# Orbit_I_AnalougeEngine_V1_0.net
KiCad netlist of a schematic drawn in EAGLE
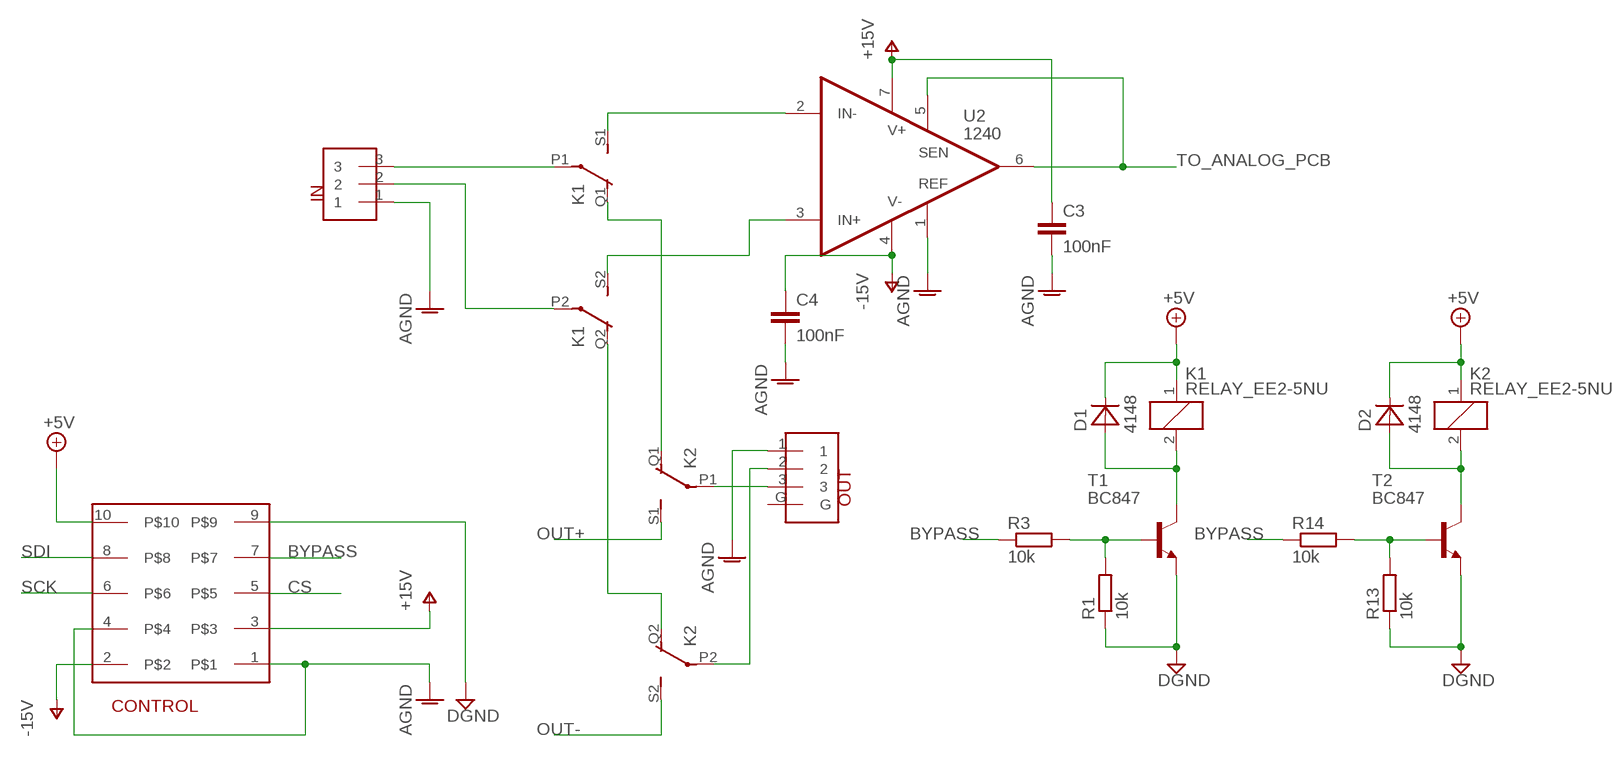
[diagram p0: schematic, sheet 1]
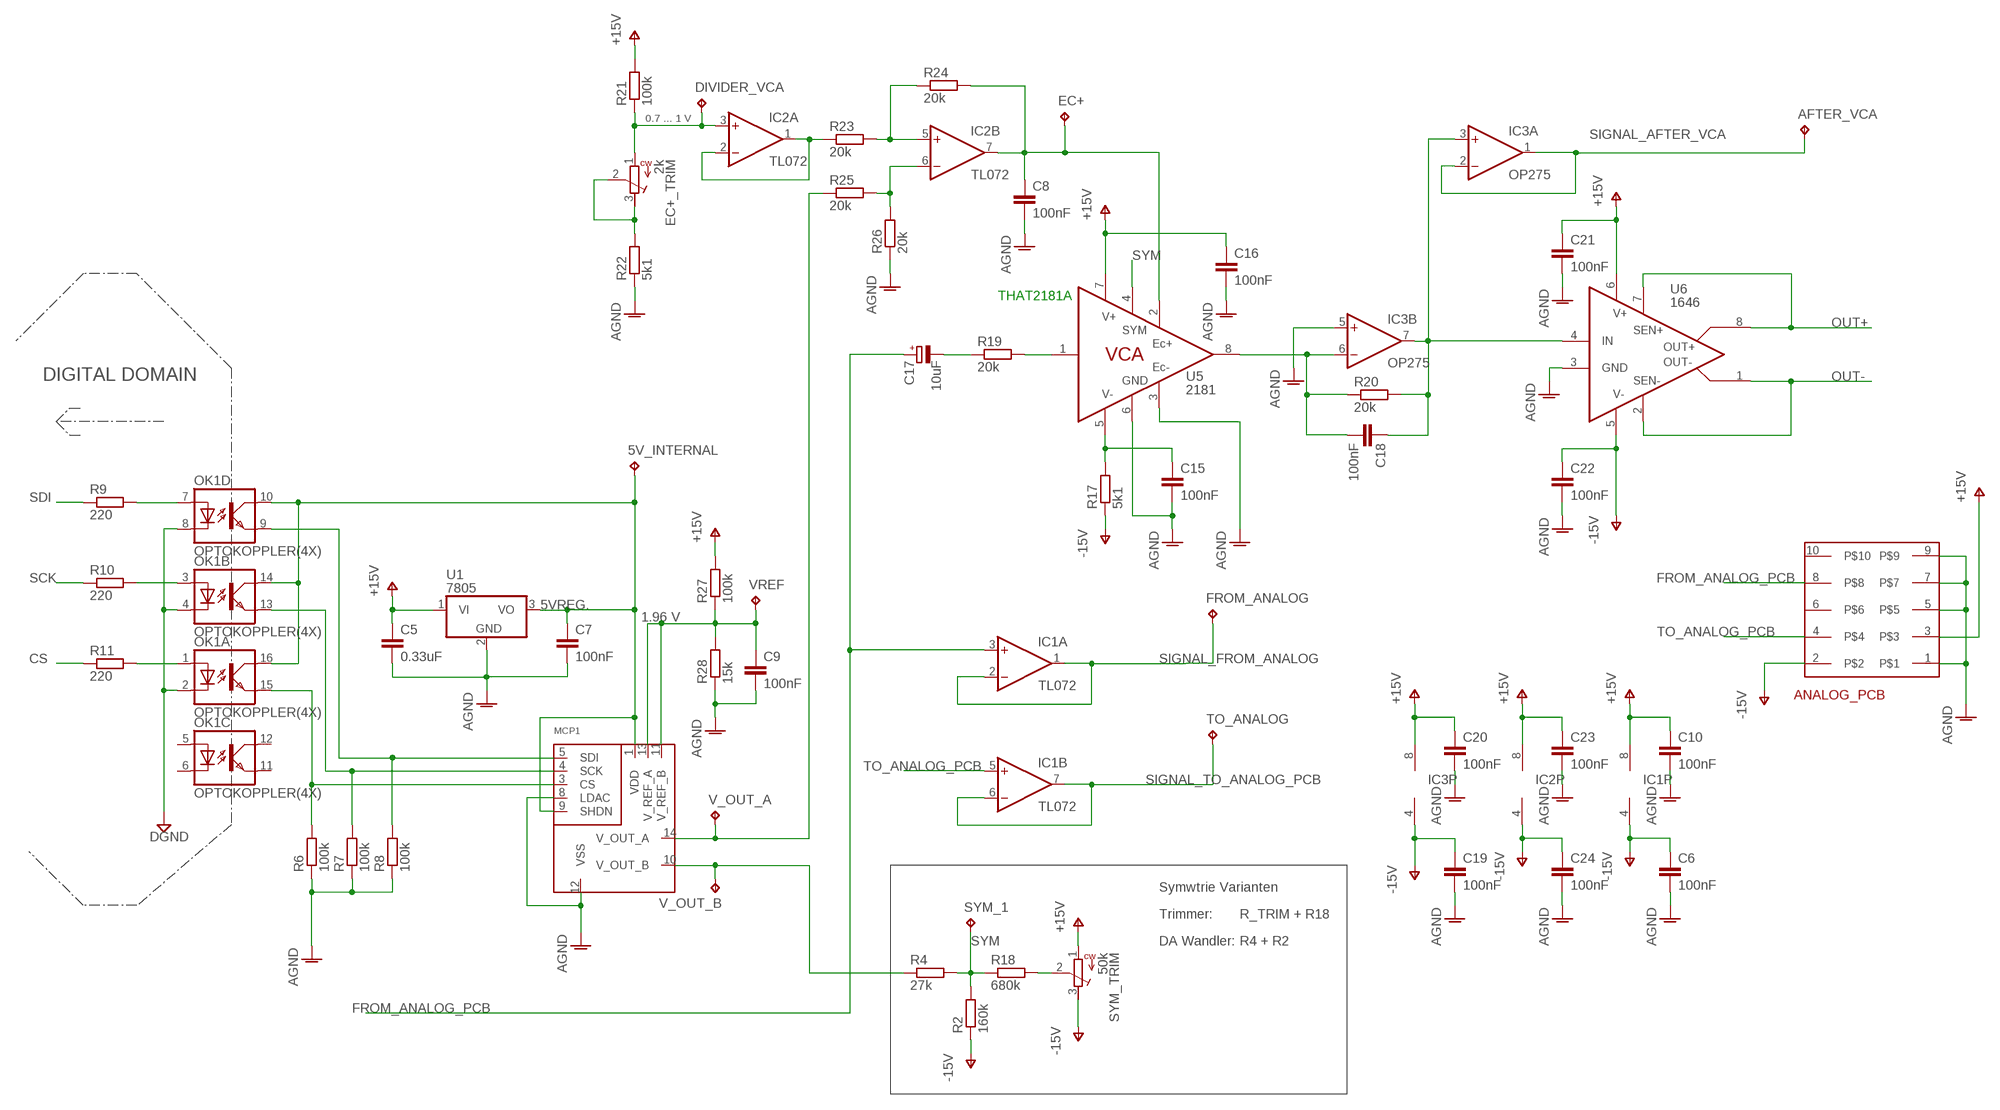
[diagram p1: schematic, sheet 2]

(export (version "E")
  (design (tool "Eeschema 10.0.6"))
  (components
    (comp (ref "C3")
      (value "100nF")
      (footprint "eagle-import:C0603")
      (libsource (lib "eagle-import") (part "KONDENSATOR_0603"))
    )
    (comp (ref "C4")
      (value "100nF")
      (footprint "eagle-import:C0603")
      (libsource (lib "eagle-import") (part "KONDENSATOR_0603"))
    )
    (comp (ref "CONTROL")
      (value "10PIN_HEADER_SMD")
      (footprint "eagle-import:87832-10")
      (libsource (lib "eagle-import") (part "10PIN_HEADER_SMD"))
    )
    (comp (ref "D1")
      (value "4148")
      (footprint "eagle-import:SOD323-R")
      (libsource (lib "eagle-import") (part "4148_SOD323"))
    )
    (comp (ref "D2")
      (value "4148")
      (footprint "eagle-import:SOD323-R")
      (libsource (lib "eagle-import") (part "4148_SOD323"))
    )
    (comp (ref "IN")
      (value "NEUTRIK_NC3FAH")
      (footprint "eagle-import:NEUTRIK_NC3FAH")
      (libsource (lib "eagle-import") (part "NEUTRIK_NC3FAH"))
    )
    (comp (ref "K1")
      (value "RELAY_EE2-5NU")
      (footprint "eagle-import:351")
      (libsource (lib "eagle-import") (part "RELAY_EE2-5NU"))
    )
    (comp (ref "K2")
      (value "RELAY_EE2-5NU")
      (footprint "eagle-import:351")
      (libsource (lib "eagle-import") (part "RELAY_EE2-5NU"))
    )
    (comp (ref "OUT")
      (value "NEUTRIK_NC3MAH")
      (footprint "eagle-import:NEUTRIK_NC3MAH")
      (libsource (lib "eagle-import") (part "NEUTRIK_NC3MAH"))
    )
    (comp (ref "R1")
      (value "10k")
      (footprint "eagle-import:R0805")
      (libsource (lib "eagle-import") (part "WIDERSTAND_0805R0805"))
    )
    (comp (ref "R3")
      (value "10k")
      (footprint "eagle-import:R0805")
      (libsource (lib "eagle-import") (part "WIDERSTAND_0805R0805"))
    )
    (comp (ref "R13")
      (value "10k")
      (footprint "eagle-import:R0805")
      (libsource (lib "eagle-import") (part "WIDERSTAND_0805R0805"))
    )
    (comp (ref "R14")
      (value "10k")
      (footprint "eagle-import:R0805")
      (libsource (lib "eagle-import") (part "WIDERSTAND_0805R0805"))
    )
    (comp (ref "T1")
      (value "BC847")
      (footprint "eagle-import:SOT23")
      (libsource (lib "eagle-import") (part "BC847"))
    )
    (comp (ref "T2")
      (value "BC847")
      (footprint "eagle-import:SOT23")
      (libsource (lib "eagle-import") (part "BC847"))
    )
    (comp (ref "U2")
      (value "1240")
      (footprint "eagle-import:SO08")
      (libsource (lib "eagle-import") (part "THAT1240SO8-U"))
    )
    (comp (ref "5V_INTERNAL")
      (value "TPTHT")
      (footprint "eagle-import:THT_PIN")
      (libsource (lib "eagle-import") (part "TPTHT"))
    )
    (comp (ref "AFTER_VCA")
      (value "TPTHT")
      (footprint "eagle-import:THT_PIN")
      (libsource (lib "eagle-import") (part "TPTHT"))
    )
    (comp (ref "ANALOG_PCB")
      (value "10PIN_HEADER_SMD")
      (footprint "eagle-import:87832-10")
      (libsource (lib "eagle-import") (part "10PIN_HEADER_SMD"))
    )
    (comp (ref "C5")
      (value "0.33uF")
      (footprint "eagle-import:C0603")
      (libsource (lib "eagle-import") (part "KONDENSATOR_0603"))
    )
    (comp (ref "C6")
      (value "100nF")
      (footprint "eagle-import:C0603")
      (libsource (lib "eagle-import") (part "KONDENSATOR_0603"))
    )
    (comp (ref "C7")
      (value "100nF")
      (footprint "eagle-import:C0603")
      (libsource (lib "eagle-import") (part "KONDENSATOR_0603"))
    )
    (comp (ref "C8")
      (value "100nF")
      (footprint "eagle-import:C0603")
      (libsource (lib "eagle-import") (part "KONDENSATOR_0603"))
    )
    (comp (ref "C9")
      (value "100nF")
      (footprint "eagle-import:C0603")
      (libsource (lib "eagle-import") (part "KONDENSATOR_0603"))
    )
    (comp (ref "C10")
      (value "100nF")
      (footprint "eagle-import:C0603")
      (libsource (lib "eagle-import") (part "KONDENSATOR_0603"))
    )
    (comp (ref "C15")
      (value "100nF")
      (footprint "eagle-import:C0603")
      (libsource (lib "eagle-import") (part "KONDENSATOR_0603"))
    )
    (comp (ref "C16")
      (value "100nF")
      (footprint "eagle-import:C0603")
      (libsource (lib "eagle-import") (part "KONDENSATOR_0603"))
    )
    (comp (ref "C17")
      (value "10uF")
      (footprint "eagle-import:153CLV-0605")
      (libsource (lib "eagle-import") (part "SMD_ELCTROLYTIC"))
    )
    (comp (ref "C18")
      (value "100nF")
      (footprint "eagle-import:C0603")
      (libsource (lib "eagle-import") (part "KONDENSATOR_0603"))
    )
    (comp (ref "C19")
      (value "100nF")
      (footprint "eagle-import:C0603")
      (libsource (lib "eagle-import") (part "KONDENSATOR_0603"))
    )
    (comp (ref "C20")
      (value "100nF")
      (footprint "eagle-import:C0603")
      (libsource (lib "eagle-import") (part "KONDENSATOR_0603"))
    )
    (comp (ref "C21")
      (value "100nF")
      (footprint "eagle-import:C0603")
      (libsource (lib "eagle-import") (part "KONDENSATOR_0603"))
    )
    (comp (ref "C22")
      (value "100nF")
      (footprint "eagle-import:C0603")
      (libsource (lib "eagle-import") (part "KONDENSATOR_0603"))
    )
    (comp (ref "C23")
      (value "100nF")
      (footprint "eagle-import:C0603")
      (libsource (lib "eagle-import") (part "KONDENSATOR_0603"))
    )
    (comp (ref "C24")
      (value "100nF")
      (footprint "eagle-import:C0603")
      (libsource (lib "eagle-import") (part "KONDENSATOR_0603"))
    )
    (comp (ref "DIVIDER_VCA")
      (value "TPTHT")
      (footprint "eagle-import:THT_PIN")
      (libsource (lib "eagle-import") (part "TPTHT"))
    )
    (comp (ref "EC+")
      (value "TPTHT")
      (footprint "eagle-import:THT_PIN")
      (libsource (lib "eagle-import") (part "TPTHT"))
    )
    (comp (ref "EC+_TRIM")
      (value "2k")
      (footprint "eagle-import:RTRIM4G_J")
      (libsource (lib "eagle-import") (part "R_TRIMMER_SMD"))
    )
    (comp (ref "FROM_ANALOG")
      (value "TPTHT")
      (footprint "eagle-import:THT_PIN")
      (libsource (lib "eagle-import") (part "TPTHT"))
    )
    (comp (ref "IC1")
      (value "TL072")
      (footprint "eagle-import:SOIC8")
      (libsource (lib "eagle-import") (part "TL072"))
    )
    (comp (ref "IC2")
      (value "TL072")
      (footprint "eagle-import:SOIC8")
      (libsource (lib "eagle-import") (part "TL072"))
    )
    (comp (ref "IC3")
      (value "OP275")
      (footprint "eagle-import:SOIC8")
      (libsource (lib "eagle-import") (part "OP275"))
    )
    (comp (ref "MCP1")
      (value "MCP4922")
      (footprint "eagle-import:SOIC16")
      (libsource (lib "eagle-import") (part "MCP4922"))
    )
    (comp (ref "OK1")
      (value "OPTOKOPPLER(4X)")
      (footprint "eagle-import:SOIC16")
      (libsource (lib "eagle-import") (part "OPTOKOPPLER(4X)"))
    )
    (comp (ref "R2")
      (value "160k")
      (footprint "eagle-import:R0805")
      (libsource (lib "eagle-import") (part "WIDERSTAND_0805R0805"))
    )
    (comp (ref "R4")
      (value "27k")
      (footprint "eagle-import:R0805")
      (libsource (lib "eagle-import") (part "WIDERSTAND_0805R0805"))
    )
    (comp (ref "R6")
      (value "100k")
      (footprint "eagle-import:R0805")
      (libsource (lib "eagle-import") (part "WIDERSTAND_0805R0805"))
    )
    (comp (ref "R7")
      (value "100k")
      (footprint "eagle-import:R0805")
      (libsource (lib "eagle-import") (part "WIDERSTAND_0805R0805"))
    )
    (comp (ref "R8")
      (value "100k")
      (footprint "eagle-import:R0805")
      (libsource (lib "eagle-import") (part "WIDERSTAND_0805R0805"))
    )
    (comp (ref "R9")
      (value "220")
      (footprint "eagle-import:R0805")
      (libsource (lib "eagle-import") (part "WIDERSTAND_0805R0805"))
    )
    (comp (ref "R10")
      (value "220")
      (footprint "eagle-import:R0805")
      (libsource (lib "eagle-import") (part "WIDERSTAND_0805R0805"))
    )
    (comp (ref "R11")
      (value "220")
      (footprint "eagle-import:R0805")
      (libsource (lib "eagle-import") (part "WIDERSTAND_0805R0805"))
    )
    (comp (ref "R17")
      (value "5k1")
      (footprint "eagle-import:R0805")
      (libsource (lib "eagle-import") (part "WIDERSTAND_0805R0805"))
    )
    (comp (ref "R18")
      (value "680k")
      (footprint "eagle-import:R0805")
      (libsource (lib "eagle-import") (part "WIDERSTAND_0805R0805"))
    )
    (comp (ref "R19")
      (value "20k")
      (footprint "eagle-import:R0805")
      (libsource (lib "eagle-import") (part "WIDERSTAND_0805R0805"))
    )
    (comp (ref "R20")
      (value "20k")
      (footprint "eagle-import:R0805")
      (libsource (lib "eagle-import") (part "WIDERSTAND_0805R0805"))
    )
    (comp (ref "R21")
      (value "100k")
      (footprint "eagle-import:R0805")
      (libsource (lib "eagle-import") (part "WIDERSTAND_0805R0805"))
    )
    (comp (ref "R22")
      (value "5k1")
      (footprint "eagle-import:R0805")
      (libsource (lib "eagle-import") (part "WIDERSTAND_0805R0805"))
    )
    (comp (ref "R23")
      (value "20k")
      (footprint "eagle-import:R0805")
      (libsource (lib "eagle-import") (part "WIDERSTAND_0805R0805"))
    )
    (comp (ref "R24")
      (value "20k")
      (footprint "eagle-import:R0805")
      (libsource (lib "eagle-import") (part "WIDERSTAND_0805R0805"))
    )
    (comp (ref "R25")
      (value "20k")
      (footprint "eagle-import:R0805")
      (libsource (lib "eagle-import") (part "WIDERSTAND_0805R0805"))
    )
    (comp (ref "R26")
      (value "20k")
      (footprint "eagle-import:R0805")
      (libsource (lib "eagle-import") (part "WIDERSTAND_0805R0805"))
    )
    (comp (ref "R27")
      (value "100k")
      (footprint "eagle-import:R0805")
      (libsource (lib "eagle-import") (part "WIDERSTAND_0805R0805"))
    )
    (comp (ref "R28")
      (value "15k")
      (footprint "eagle-import:R0805")
      (libsource (lib "eagle-import") (part "WIDERSTAND_0805R0805"))
    )
    (comp (ref "SYM_1")
      (value "TPTHT")
      (footprint "eagle-import:THT_PIN")
      (libsource (lib "eagle-import") (part "TPTHT"))
    )
    (comp (ref "SYM_TRIM")
      (value "50k")
      (footprint "eagle-import:RTRIM4G_J")
      (libsource (lib "eagle-import") (part "R_TRIMMER_SMD"))
    )
    (comp (ref "TO_ANALOG")
      (value "TPTHT")
      (footprint "eagle-import:THT_PIN")
      (libsource (lib "eagle-import") (part "TPTHT"))
    )
    (comp (ref "U1")
      (value "7805")
      (footprint "eagle-import:TO252")
      (libsource (lib "eagle-import") (part "78"))
    )
    (comp (ref "U5")
      (value "2181")
      (footprint "eagle-import:SO08")
      (libsource (lib "eagle-import") (part "THAT2181S"))
    )
    (comp (ref "U6")
      (value "1646")
      (footprint "eagle-import:SO08")
      (libsource (lib "eagle-import") (part "THAT1646SO8-U"))
    )
    (comp (ref "VREF")
      (value "TPTHT")
      (footprint "eagle-import:THT_PIN")
      (libsource (lib "eagle-import") (part "TPTHT"))
    )
    (comp (ref "V_OUT_A")
      (value "TPTHT")
      (footprint "eagle-import:THT_PIN")
      (libsource (lib "eagle-import") (part "TPTHT"))
    )
    (comp (ref "V_OUT_B")
      (value "TPTHT")
      (footprint "eagle-import:THT_PIN")
      (libsource (lib "eagle-import") (part "TPTHT"))
    )
  )
  (nets
    (net (code "1") (name "+5V") (class "Default")
      (node (ref "CONTROL") (pin "10") (pinfunction "P$10_10") (pintype "bidirectional"))
      (node (ref "D1") (pin "C") (pinfunction "C_C") (pintype "passive"))
      (node (ref "D2") (pin "C") (pinfunction "C_C") (pintype "passive"))
      (node (ref "K1") (pin "1") (pinfunction "1_1") (pintype "passive"))
      (node (ref "K2") (pin "1") (pinfunction "1_1") (pintype "passive"))
    )
    (net (code "2") (name "5VREG.") (class "Default")
      (node (ref "5V_INTERNAL") (pin "P$1") (pinfunction "TP_P$1") (pintype "input"))
      (node (ref "C7") (pin "1") (pinfunction "1_1") (pintype "passive"))
      (node (ref "MCP1") (pin "1") (pinfunction "VDD_1") (pintype "input"))
      (node (ref "MCP1") (pin "9") (pinfunction "SHDN_9") (pintype "input"))
      (node (ref "OK1") (pin "10") (pinfunction "COL_10") (pintype "passive"))
      (node (ref "OK1") (pin "14") (pinfunction "COL_14") (pintype "passive"))
      (node (ref "OK1") (pin "16") (pinfunction "COL_16") (pintype "passive"))
      (node (ref "U1") (pin "3") (pinfunction "VO_3") (pintype "passive"))
    )
    (net (code "3") (name "AGND") (class "Default")
      (node (ref "ANALOG_PCB") (pin "1") (pinfunction "P$1_1") (pintype "bidirectional"))
      (node (ref "ANALOG_PCB") (pin "5") (pinfunction "P$5_5") (pintype "bidirectional"))
      (node (ref "ANALOG_PCB") (pin "7") (pinfunction "P$7_7") (pintype "bidirectional"))
      (node (ref "ANALOG_PCB") (pin "9") (pinfunction "P$9_9") (pintype "bidirectional"))
      (node (ref "C10") (pin "2") (pinfunction "2_2") (pintype "passive"))
      (node (ref "C15") (pin "2") (pinfunction "2_2") (pintype "passive"))
      (node (ref "C16") (pin "2") (pinfunction "2_2") (pintype "passive"))
      (node (ref "C19") (pin "2") (pinfunction "2_2") (pintype "passive"))
      (node (ref "C20") (pin "2") (pinfunction "2_2") (pintype "passive"))
      (node (ref "C21") (pin "2") (pinfunction "2_2") (pintype "passive"))
      (node (ref "C22") (pin "2") (pinfunction "2_2") (pintype "passive"))
      (node (ref "C23") (pin "2") (pinfunction "2_2") (pintype "passive"))
      (node (ref "C24") (pin "2") (pinfunction "2_2") (pintype "passive"))
      (node (ref "C3") (pin "2") (pinfunction "2_2") (pintype "passive"))
      (node (ref "C4") (pin "2") (pinfunction "2_2") (pintype "passive"))
      (node (ref "C5") (pin "2") (pinfunction "2_2") (pintype "passive"))
      (node (ref "C6") (pin "2") (pinfunction "2_2") (pintype "passive"))
      (node (ref "C7") (pin "2") (pinfunction "2_2") (pintype "passive"))
      (node (ref "C8") (pin "2") (pinfunction "2_2") (pintype "passive"))
      (node (ref "C9") (pin "2") (pinfunction "2_2") (pintype "passive"))
      (node (ref "CONTROL") (pin "1") (pinfunction "P$1_1") (pintype "bidirectional"))
      (node (ref "CONTROL") (pin "4") (pinfunction "P$4_4") (pintype "bidirectional"))
      (node (ref "IC3") (pin "5") (pinfunction "+IN_5") (pintype "input"))
      (node (ref "IN") (pin "1") (pinfunction "1_1") (pintype "bidirectional"))
      (node (ref "MCP1") (pin "12") (pinfunction "VSS_12") (pintype "input"))
      (node (ref "MCP1") (pin "8") (pinfunction "LDAC_8") (pintype "input"))
      (node (ref "OUT") (pin "1") (pinfunction "1_1") (pintype "bidirectional"))
      (node (ref "R22") (pin "1") (pinfunction "1_1") (pintype "passive"))
      (node (ref "R26") (pin "1") (pinfunction "1_1") (pintype "passive"))
      (node (ref "R28") (pin "1") (pinfunction "1_1") (pintype "passive"))
      (node (ref "R6") (pin "1") (pinfunction "1_1") (pintype "passive"))
      (node (ref "R7") (pin "1") (pinfunction "1_1") (pintype "passive"))
      (node (ref "R8") (pin "1") (pinfunction "1_1") (pintype "passive"))
      (node (ref "U1") (pin "2") (pinfunction "GND_2") (pintype "passive"))
      (node (ref "U2") (pin "1") (pinfunction "REF_1") (pintype "passive"))
      (node (ref "U5") (pin "3") (pinfunction "EC-_3") (pintype "output"))
      (node (ref "U5") (pin "6") (pinfunction "GND_6") (pintype "passive"))
      (node (ref "U6") (pin "3") (pinfunction "GND_3") (pintype "input"))
    )
    (net (code "4") (name "BYPASS") (class "Default")
      (node (ref "CONTROL") (pin "7") (pinfunction "P$7_7") (pintype "bidirectional"))
      (node (ref "R14") (pin "1") (pinfunction "1_1") (pintype "passive"))
      (node (ref "R3") (pin "1") (pinfunction "1_1") (pintype "passive"))
    )
    (net (code "5") (name "CS") (class "Default")
      (node (ref "CONTROL") (pin "5") (pinfunction "P$5_5") (pintype "bidirectional"))
      (node (ref "R11") (pin "1") (pinfunction "1_1") (pintype "passive"))
    )
    (net (code "6") (name "DGND") (class "Default")
      (node (ref "CONTROL") (pin "9") (pinfunction "P$9_9") (pintype "bidirectional"))
      (node (ref "OK1") (pin "2") (pinfunction "C_2") (pintype "passive"))
      (node (ref "OK1") (pin "4") (pinfunction "C_4") (pintype "passive"))
      (node (ref "OK1") (pin "8") (pinfunction "C_8") (pintype "passive"))
      (node (ref "R1") (pin "1") (pinfunction "1_1") (pintype "passive"))
      (node (ref "R13") (pin "1") (pinfunction "1_1") (pintype "passive"))
      (node (ref "T1") (pin "2") (pinfunction "E_2") (pintype "passive"))
      (node (ref "T2") (pin "2") (pinfunction "E_2") (pintype "passive"))
    )
    (net (code "7") (name "FROM_ANALOG_PCB") (class "Default")
      (node (ref "ANALOG_PCB") (pin "8") (pinfunction "P$8_8") (pintype "bidirectional"))
      (node (ref "C17") (pin "+") (pinfunction "+_+") (pintype "passive"))
      (node (ref "IC1") (pin "3") (pinfunction "+IN_3") (pintype "input"))
    )
    (net (code "8") (name "Net-(C17-Pad-)") (class "Default")
      (node (ref "C17") (pin "-") (pinfunction "-_-") (pintype "passive"))
      (node (ref "R19") (pin "1") (pinfunction "1_1") (pintype "passive"))
    )
    (net (code "9") (name "Net-(DIVIDER_VCA-TP)") (class "Default")
      (node (ref "DIVIDER_VCA") (pin "P$1") (pinfunction "TP_P$1") (pintype "input"))
      (node (ref "EC+_TRIM") (pin "1") (pinfunction "1_1") (pintype "passive"))
      (node (ref "IC2") (pin "3") (pinfunction "+IN_3") (pintype "input"))
      (node (ref "R21") (pin "1") (pinfunction "1_1") (pintype "passive"))
    )
    (net (code "10") (name "Net-(EC+-TP)") (class "Default")
      (node (ref "C8") (pin "1") (pinfunction "1_1") (pintype "passive"))
      (node (ref "EC+") (pin "P$1") (pinfunction "TP_P$1") (pintype "input"))
      (node (ref "IC2") (pin "7") (pinfunction "OUT_7") (pintype "output"))
      (node (ref "R24") (pin "2") (pinfunction "2_2") (pintype "passive"))
      (node (ref "U5") (pin "2") (pinfunction "EC+_2") (pintype "passive"))
    )
    (net (code "11") (name "Net-(EC+_TRIM-Pad2)") (class "Default")
      (node (ref "EC+_TRIM") (pin "2") (pinfunction "2_2") (pintype "passive"))
      (node (ref "EC+_TRIM") (pin "3") (pinfunction "3_3") (pintype "passive"))
      (node (ref "R22") (pin "2") (pinfunction "2_2") (pintype "passive"))
    )
    (net (code "12") (name "Net-(IC2A--IN)") (class "Default")
      (node (ref "IC2") (pin "1") (pinfunction "OUT_1") (pintype "output"))
      (node (ref "IC2") (pin "2") (pinfunction "-IN_2") (pintype "input"))
      (node (ref "R23") (pin "1") (pinfunction "1_1") (pintype "passive"))
    )
    (net (code "13") (name "Net-(IC2B-+IN)") (class "Default")
      (node (ref "IC2") (pin "5") (pinfunction "+IN_5") (pintype "input"))
      (node (ref "R23") (pin "2") (pinfunction "2_2") (pintype "passive"))
      (node (ref "R24") (pin "1") (pinfunction "1_1") (pintype "passive"))
    )
    (net (code "14") (name "Net-(IC2B--IN)") (class "Default")
      (node (ref "IC2") (pin "6") (pinfunction "-IN_6") (pintype "input"))
      (node (ref "R25") (pin "2") (pinfunction "2_2") (pintype "passive"))
      (node (ref "R26") (pin "2") (pinfunction "2_2") (pintype "passive"))
    )
    (net (code "15") (name "Net-(IC3A-+IN)") (class "Default")
      (node (ref "C18") (pin "1") (pinfunction "1_1") (pintype "passive"))
      (node (ref "IC3") (pin "3") (pinfunction "+IN_3") (pintype "input"))
      (node (ref "IC3") (pin "7") (pinfunction "OUT_7") (pintype "output"))
      (node (ref "R20") (pin "2") (pinfunction "2_2") (pintype "passive"))
      (node (ref "U6") (pin "4") (pinfunction "IN_4") (pintype "input"))
    )
    (net (code "16") (name "Net-(IC3B--IN)") (class "Default")
      (node (ref "C18") (pin "2") (pinfunction "2_2") (pintype "passive"))
      (node (ref "IC3") (pin "6") (pinfunction "-IN_6") (pintype "input"))
      (node (ref "R20") (pin "1") (pinfunction "1_1") (pintype "passive"))
      (node (ref "U5") (pin "8") (pinfunction "OUT_8") (pintype "output"))
    )
    (net (code "17") (name "Net-(K1B-O)") (class "Default")
      (node (ref "K1") (pin "Q1") (pinfunction "O_Q1") (pintype "passive"))
      (node (ref "K2") (pin "Q1") (pinfunction "O_Q1") (pintype "passive"))
    )
    (net (code "18") (name "Net-(K1B-P)") (class "Default")
      (node (ref "IN") (pin "3") (pinfunction "3_3") (pintype "bidirectional"))
      (node (ref "K1") (pin "P1") (pinfunction "P_P1") (pintype "passive"))
    )
    (net (code "19") (name "Net-(K1B-S)") (class "Default")
      (node (ref "K1") (pin "S1") (pinfunction "S_S1") (pintype "passive"))
      (node (ref "U2") (pin "2") (pinfunction "IN-_2") (pintype "input"))
    )
    (net (code "20") (name "Net-(K1C-O)") (class "Default")
      (node (ref "K1") (pin "Q2") (pinfunction "O_Q2") (pintype "passive"))
      (node (ref "K2") (pin "Q2") (pinfunction "O_Q2") (pintype "passive"))
    )
    (net (code "21") (name "Net-(K1C-P)") (class "Default")
      (node (ref "IN") (pin "2") (pinfunction "2_2") (pintype "bidirectional"))
      (node (ref "K1") (pin "P2") (pinfunction "P_P2") (pintype "passive"))
    )
    (net (code "22") (name "Net-(K1C-S)") (class "Default")
      (node (ref "K1") (pin "S2") (pinfunction "S_S2") (pintype "passive"))
      (node (ref "U2") (pin "3") (pinfunction "IN+_3") (pintype "input"))
    )
    (net (code "23") (name "Net-(K2B-P)") (class "Default")
      (node (ref "K2") (pin "P1") (pinfunction "P_P1") (pintype "passive"))
      (node (ref "OUT") (pin "3") (pinfunction "3_3") (pintype "bidirectional"))
    )
    (net (code "24") (name "Net-(K2C-P)") (class "Default")
      (node (ref "K2") (pin "P2") (pinfunction "P_P2") (pintype "passive"))
      (node (ref "OUT") (pin "2") (pinfunction "2_2") (pintype "bidirectional"))
    )
    (net (code "25") (name "Net-(MCP1-CS)") (class "Default")
      (node (ref "MCP1") (pin "3") (pinfunction "CS_3") (pintype "input"))
      (node (ref "OK1") (pin "15") (pinfunction "EMIT_15") (pintype "passive"))
      (node (ref "R6") (pin "2") (pinfunction "2_2") (pintype "passive"))
    )
    (net (code "26") (name "Net-(MCP1-SCK)") (class "Default")
      (node (ref "MCP1") (pin "4") (pinfunction "SCK_4") (pintype "input"))
      (node (ref "OK1") (pin "13") (pinfunction "EMIT_13") (pintype "passive"))
      (node (ref "R7") (pin "2") (pinfunction "2_2") (pintype "passive"))
    )
    (net (code "27") (name "Net-(MCP1-SDI)") (class "Default")
      (node (ref "MCP1") (pin "5") (pinfunction "SDI_5") (pintype "input"))
      (node (ref "OK1") (pin "9") (pinfunction "EMIT_9") (pintype "passive"))
      (node (ref "R8") (pin "2") (pinfunction "2_2") (pintype "passive"))
    )
    (net (code "28") (name "Net-(MCP1-V_OUT_A)") (class "Default")
      (node (ref "MCP1") (pin "14") (pinfunction "V_OUT_A_14") (pintype "input"))
      (node (ref "R25") (pin "1") (pinfunction "1_1") (pintype "passive"))
      (node (ref "V_OUT_A") (pin "P$1") (pinfunction "TP_P$1") (pintype "input"))
    )
    (net (code "29") (name "Net-(MCP1-V_OUT_B)") (class "Default")
      (node (ref "MCP1") (pin "10") (pinfunction "V_OUT_B_10") (pintype "input"))
      (node (ref "R4") (pin "1") (pinfunction "1_1") (pintype "passive"))
      (node (ref "V_OUT_B") (pin "P$1") (pinfunction "TP_P$1") (pintype "input"))
    )
    (net (code "30") (name "Net-(MCP1-V_REF_A)") (class "Default")
      (node (ref "C9") (pin "1") (pinfunction "1_1") (pintype "passive"))
      (node (ref "MCP1") (pin "11") (pinfunction "V_REF_B_11") (pintype "input"))
      (node (ref "MCP1") (pin "13") (pinfunction "V_REF_A_13") (pintype "input"))
      (node (ref "R27") (pin "1") (pinfunction "1_1") (pintype "passive"))
      (node (ref "R28") (pin "2") (pinfunction "2_2") (pintype "passive"))
      (node (ref "VREF") (pin "P$1") (pinfunction "TP_P$1") (pintype "input"))
    )
    (net (code "31") (name "Net-(OK1A-A)") (class "Default")
      (node (ref "OK1") (pin "1") (pinfunction "A_1") (pintype "passive"))
      (node (ref "R11") (pin "2") (pinfunction "2_2") (pintype "passive"))
    )
    (net (code "32") (name "Net-(OK1B-A)") (class "Default")
      (node (ref "OK1") (pin "3") (pinfunction "A_3") (pintype "passive"))
      (node (ref "R10") (pin "2") (pinfunction "2_2") (pintype "passive"))
    )
    (net (code "33") (name "Net-(OK1D-A)") (class "Default")
      (node (ref "OK1") (pin "7") (pinfunction "A_7") (pintype "passive"))
      (node (ref "R9") (pin "2") (pinfunction "2_2") (pintype "passive"))
    )
    (net (code "34") (name "Net-(R18-Pad2)") (class "Default")
      (node (ref "R18") (pin "2") (pinfunction "2_2") (pintype "passive"))
      (node (ref "SYM_TRIM") (pin "2") (pinfunction "2_2") (pintype "passive"))
    )
    (net (code "35") (name "Net-(T1-B)") (class "Default")
      (node (ref "R1") (pin "2") (pinfunction "2_2") (pintype "passive"))
      (node (ref "R3") (pin "2") (pinfunction "2_2") (pintype "passive"))
      (node (ref "T1") (pin "1") (pinfunction "B_1") (pintype "passive"))
    )
    (net (code "36") (name "Net-(T1-C)") (class "Default")
      (node (ref "D1") (pin "A") (pinfunction "A_A") (pintype "passive"))
      (node (ref "K1") (pin "2") (pinfunction "2_2") (pintype "passive"))
      (node (ref "T1") (pin "3") (pinfunction "C_3") (pintype "passive"))
    )
    (net (code "37") (name "Net-(T2-B)") (class "Default")
      (node (ref "R13") (pin "2") (pinfunction "2_2") (pintype "passive"))
      (node (ref "R14") (pin "2") (pinfunction "2_2") (pintype "passive"))
      (node (ref "T2") (pin "1") (pinfunction "B_1") (pintype "passive"))
    )
    (net (code "38") (name "Net-(T2-C)") (class "Default")
      (node (ref "D2") (pin "A") (pinfunction "A_A") (pintype "passive"))
      (node (ref "K2") (pin "2") (pinfunction "2_2") (pintype "passive"))
      (node (ref "T2") (pin "3") (pinfunction "C_3") (pintype "passive"))
    )
    (net (code "39") (name "Net-(U5-IN)") (class "Default")
      (node (ref "R19") (pin "2") (pinfunction "2_2") (pintype "passive"))
      (node (ref "U5") (pin "1") (pinfunction "IN_1") (pintype "input"))
    )
    (net (code "40") (name "Net-(U5-V-)") (class "Default")
      (node (ref "C15") (pin "1") (pinfunction "1_1") (pintype "passive"))
      (node (ref "R17") (pin "2") (pinfunction "2_2") (pintype "passive"))
      (node (ref "U5") (pin "5") (pinfunction "V-_5") (pintype "power_in"))
    )
    (net (code "41") (name "OUT+") (class "Default")
      (node (ref "K2") (pin "S1") (pinfunction "S_S1") (pintype "passive"))
      (node (ref "U6") (pin "7") (pinfunction "SEN+_7") (pintype "output"))
      (node (ref "U6") (pin "8") (pinfunction "OUT+_8") (pintype "output"))
    )
    (net (code "42") (name "OUT-") (class "Default")
      (node (ref "K2") (pin "S2") (pinfunction "S_S2") (pintype "passive"))
      (node (ref "U6") (pin "1") (pinfunction "OUT-_1") (pintype "output"))
      (node (ref "U6") (pin "2") (pinfunction "SEN-_2") (pintype "passive"))
    )
    (net (code "43") (name "SCK") (class "Default")
      (node (ref "CONTROL") (pin "6") (pinfunction "P$6_6") (pintype "bidirectional"))
      (node (ref "R10") (pin "1") (pinfunction "1_1") (pintype "passive"))
    )
    (net (code "44") (name "SDI") (class "Default")
      (node (ref "CONTROL") (pin "8") (pinfunction "P$8_8") (pintype "bidirectional"))
      (node (ref "R9") (pin "1") (pinfunction "1_1") (pintype "passive"))
    )
    (net (code "45") (name "SIGNAL_AFTER_VCA") (class "Default")
      (node (ref "AFTER_VCA") (pin "P$1") (pinfunction "TP_P$1") (pintype "input"))
      (node (ref "IC3") (pin "1") (pinfunction "OUT_1") (pintype "output"))
      (node (ref "IC3") (pin "2") (pinfunction "-IN_2") (pintype "input"))
    )
    (net (code "46") (name "SIGNAL_FROM_ANALOG") (class "Default")
      (node (ref "FROM_ANALOG") (pin "P$1") (pinfunction "TP_P$1") (pintype "input"))
      (node (ref "IC1") (pin "1") (pinfunction "OUT_1") (pintype "output"))
      (node (ref "IC1") (pin "2") (pinfunction "-IN_2") (pintype "input"))
    )
    (net (code "47") (name "SIGNAL_TO_ANALOG_PCB") (class "Default")
      (node (ref "IC1") (pin "6") (pinfunction "-IN_6") (pintype "input"))
      (node (ref "IC1") (pin "7") (pinfunction "OUT_7") (pintype "output"))
      (node (ref "TO_ANALOG") (pin "P$1") (pinfunction "TP_P$1") (pintype "input"))
    )
    (net (code "48") (name "SYM") (class "Default")
      (node (ref "R18") (pin "1") (pinfunction "1_1") (pintype "passive"))
      (node (ref "R2") (pin "2") (pinfunction "2_2") (pintype "passive"))
      (node (ref "R4") (pin "2") (pinfunction "2_2") (pintype "passive"))
      (node (ref "SYM_1") (pin "P$1") (pinfunction "TP_P$1") (pintype "input"))
      (node (ref "U5") (pin "4") (pinfunction "SYM_4") (pintype "passive"))
    )
    (net (code "49") (name "TO_ANALOG_PCB") (class "Default")
      (node (ref "ANALOG_PCB") (pin "4") (pinfunction "P$4_4") (pintype "bidirectional"))
      (node (ref "IC1") (pin "5") (pinfunction "+IN_5") (pintype "input"))
      (node (ref "U2") (pin "5") (pinfunction "SEN_5") (pintype "output"))
      (node (ref "U2") (pin "6") (pinfunction "OUT_6") (pintype "output"))
    )
    (net (code "50") (name "V+") (class "Default")
      (node (ref "ANALOG_PCB") (pin "3") (pinfunction "P$3_3") (pintype "bidirectional"))
      (node (ref "C10") (pin "1") (pinfunction "1_1") (pintype "passive"))
      (node (ref "C16") (pin "1") (pinfunction "1_1") (pintype "passive"))
      (node (ref "C20") (pin "1") (pinfunction "1_1") (pintype "passive"))
      (node (ref "C21") (pin "1") (pinfunction "1_1") (pintype "passive"))
      (node (ref "C23") (pin "1") (pinfunction "1_1") (pintype "passive"))
      (node (ref "C3") (pin "1") (pinfunction "1_1") (pintype "passive"))
      (node (ref "C5") (pin "1") (pinfunction "1_1") (pintype "passive"))
      (node (ref "CONTROL") (pin "3") (pinfunction "P$3_3") (pintype "bidirectional"))
      (node (ref "IC1") (pin "8") (pinfunction "V+_8") (pintype "power_in"))
      (node (ref "IC2") (pin "8") (pinfunction "V+_8") (pintype "power_in"))
      (node (ref "IC3") (pin "8") (pinfunction "V+_8") (pintype "power_in"))
      (node (ref "R21") (pin "2") (pinfunction "2_2") (pintype "passive"))
      (node (ref "R27") (pin "2") (pinfunction "2_2") (pintype "passive"))
      (node (ref "SYM_TRIM") (pin "1") (pinfunction "1_1") (pintype "passive"))
      (node (ref "U1") (pin "1") (pinfunction "VI_1") (pintype "input"))
      (node (ref "U2") (pin "7") (pinfunction "V+_7") (pintype "power_in"))
      (node (ref "U5") (pin "7") (pinfunction "V+_7") (pintype "power_in"))
      (node (ref "U6") (pin "6") (pinfunction "V+_6") (pintype "power_in"))
    )
    (net (code "51") (name "V-") (class "Default")
      (node (ref "ANALOG_PCB") (pin "2") (pinfunction "P$2_2") (pintype "bidirectional"))
      (node (ref "C19") (pin "1") (pinfunction "1_1") (pintype "passive"))
      (node (ref "C22") (pin "1") (pinfunction "1_1") (pintype "passive"))
      (node (ref "C24") (pin "1") (pinfunction "1_1") (pintype "passive"))
      (node (ref "C4") (pin "1") (pinfunction "1_1") (pintype "passive"))
      (node (ref "C6") (pin "1") (pinfunction "1_1") (pintype "passive"))
      (node (ref "CONTROL") (pin "2") (pinfunction "P$2_2") (pintype "bidirectional"))
      (node (ref "IC1") (pin "4") (pinfunction "V-_4") (pintype "power_in"))
      (node (ref "IC2") (pin "4") (pinfunction "V-_4") (pintype "power_in"))
      (node (ref "IC3") (pin "4") (pinfunction "V-_4") (pintype "power_in"))
      (node (ref "R17") (pin "1") (pinfunction "1_1") (pintype "passive"))
      (node (ref "R2") (pin "1") (pinfunction "1_1") (pintype "passive"))
      (node (ref "SYM_TRIM") (pin "3") (pinfunction "3_3") (pintype "passive"))
      (node (ref "U2") (pin "4") (pinfunction "V-_4") (pintype "power_in"))
      (node (ref "U6") (pin "5") (pinfunction "V-_5") (pintype "power_in"))
    )
    (net (code "52") (name "unconnected-(ANALOG_PCB-P$6-Pad6)") (class "Default")
      (node (ref "ANALOG_PCB") (pin "6") (pinfunction "P$6_6") (pintype "bidirectional"))
    )
    (net (code "53") (name "unconnected-(ANALOG_PCB-P$10-Pad10)") (class "Default")
      (node (ref "ANALOG_PCB") (pin "10") (pinfunction "P$10_10") (pintype "bidirectional"))
    )
    (net (code "54") (name "unconnected-(OK1C-A-Pad5)") (class "Default")
      (node (ref "OK1") (pin "5") (pinfunction "A_5") (pintype "passive"))
    )
    (net (code "55") (name "unconnected-(OK1C-C-Pad6)") (class "Default")
      (node (ref "OK1") (pin "6") (pinfunction "C_6") (pintype "passive"))
    )
    (net (code "56") (name "unconnected-(OK1C-COL-Pad12)") (class "Default")
      (node (ref "OK1") (pin "12") (pinfunction "COL_12") (pintype "passive"))
    )
    (net (code "57") (name "unconnected-(OK1C-EMIT-Pad11)") (class "Default")
      (node (ref "OK1") (pin "11") (pinfunction "EMIT_11") (pintype "passive"))
    )
    (net (code "58") (name "unconnected-(OUT-PadG)") (class "Default")
      (node (ref "OUT") (pin "G") (pinfunction "G_G") (pintype "bidirectional"))
    )
  )
)
